# regulator.net
KiCad netlist of a schematic drawn in Altium Designer
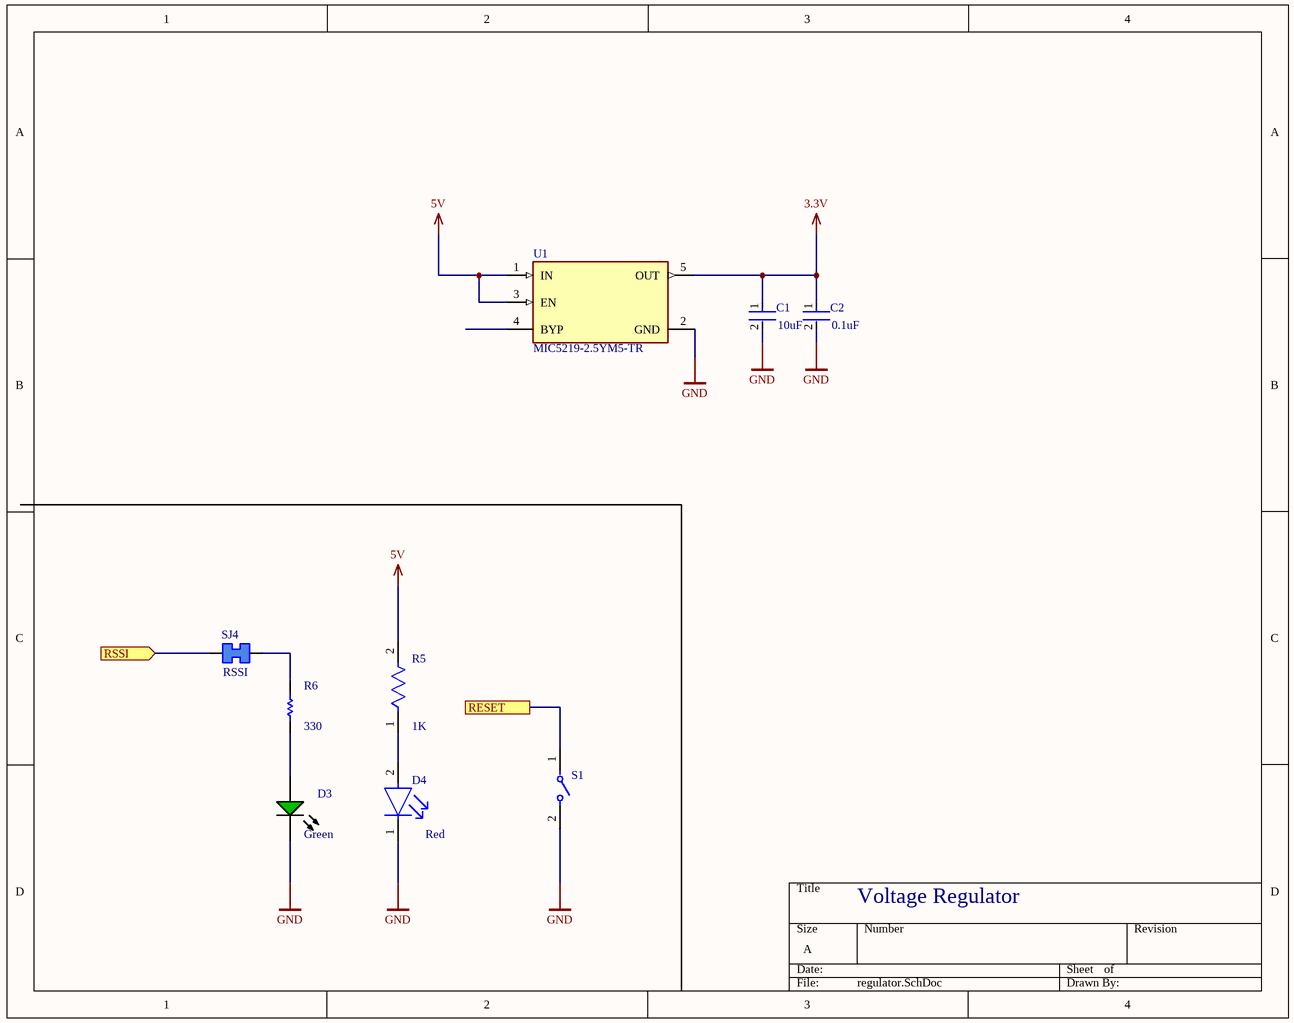
[diagram p0: regulator.SchDoc]

(export (version "E")
  (design (tool "Eeschema 10.0.6"))
  (components
    (comp (ref "C1")
      (value "10uF")
      (footprint "FP-GRM188-0_1-e0_2_0_55-IPC_A")
      (description "Chip Multilayer Ceramic Capacitors for General Purpose, 0603, 10uF, X5R, 15%, 20%, 6.3V")
      (fields (field (name "VOLTAGE") "6.3V") (field (name "TOLERANCE") "20%"))
      (libsource (lib "Altium Content Vault") (part "02cd4be3c70576c341d710602a673aa"))
    )
    (comp (ref "C2")
      (value "0.1uF")
      (footprint "FP-C0402-BB-MFG")
      (description "CAP CER 0.1UF 10V X5R 0402")
      (fields (field (name "MANUFACTURER") "Kemet") (field (name "TOLERANCE") "0.1"))
      (libsource (lib "Altium Content Vault") (part "b4654b650e69147ec39a6b967a45e02"))
    )
    (comp (ref "D3")
      (value "Green")
      (footprint "AVAG-HSMX-C170_V")
      (description "Chip LED, Green, 2.2 V, -40 to 85 degC, 2-Pin SMD, Pb-Free, Tape and Reel")
      (fields (field (name "MANUFACTURER") "Avago"))
      (libsource (lib "Altium Content Vault") (part "LED_GREEN_A1K2-2"))
    )
    (comp (ref "D4")
      (value "Red")
      (footprint "FP-HSMS-C150-MFG")
      (description "LED RED DIFFUSED CHIP SMD")
      (libsource (lib "Altium Content Vault") (part "8706943c75ba83719d021d2fdc84c58"))
    )
    (comp (ref "R5")
      (value "1K")
      (footprint "FP-ERJ1GN-IPC_C")
      (description "RES SMD 1K OHM 1% 1/20W 0201")
      (fields (field (name "TOLERANCE") "1%"))
      (libsource (lib "Altium Content Vault") (part "1029c3af85768c4190bb7ad29bc67b5"))
    )
    (comp (ref "R6")
      (value "330")
      (footprint "RESC0603X26X15ML03T05")
      (fields (field (name "PART NUMBER") "ERJ1GNF3300C") (field (name "MANUFACTURER") "Panasonic"))
      (libsource (lib "Altium Content Vault") (part "RES"))
    )
    (comp (ref "S1")
      (value "~")
      (footprint "FP-B3F-6022-MFG")
      (description "SWITCH TACTILE SPST-NO 0.05A 24V")
      (libsource (lib "Altium Content Vault") (part "bb27bde45df87f1f469753f287ef5ae"))
    )
    (comp (ref "SJ4")
      (value "RSSI")
      (footprint "Solder Jumper-Footprint-1")
      (description "2 pad Solder Jumper")
      (libsource (lib "Shuvendu Das") (part "Solder Jumper"))
    )
    (comp (ref "U1")
      (value "MIC5219-2.5YM5-TR")
      (footprint "FP-SOT23-5LD-PL-1-MFG")
      (description "MIC5219-2.5YM5-TR LDO Regulator Pos 2.5V 0.5A 5-Pin SOT-23 T/R")
      (libsource (lib "Altium Content Vault") (part "2b4562ae194ecca3f53436ab1e355a0"))
    )
  )
  (nets
    (net (code "1") (name "/RESET") (class "Default")
      (node (ref "S1") (pin "1") (pinfunction "1_1") (pintype "passive"))
    )
    (net (code "2") (name "/RSSI") (class "Default")
      (node (ref "SJ4") (pin "1") (pinfunction "1_1") (pintype "passive"))
    )
    (net (code "3") (name "3.3V") (class "Default")
      (node (ref "C1") (pin "1") (pinfunction "1_1") (pintype "passive"))
      (node (ref "C2") (pin "1") (pinfunction "1_1") (pintype "passive"))
      (node (ref "U1") (pin "5") (pinfunction "OUT_5") (pintype "output"))
    )
    (net (code "4") (name "5V") (class "Default")
      (node (ref "R5") (pin "2") (pinfunction "2_2") (pintype "passive"))
      (node (ref "U1") (pin "1") (pinfunction "IN_1") (pintype "input"))
      (node (ref "U1") (pin "3") (pinfunction "EN_3") (pintype "input"))
    )
    (net (code "5") (name "GND") (class "Default")
      (node (ref "C1") (pin "2") (pinfunction "2_2") (pintype "passive"))
      (node (ref "C2") (pin "2") (pinfunction "2_2") (pintype "passive"))
      (node (ref "D3") (pin "2") (pinfunction "K_2") (pintype "passive"))
      (node (ref "D4") (pin "1") (pinfunction "C_1") (pintype "passive"))
      (node (ref "S1") (pin "2") (pinfunction "2_2") (pintype "passive"))
      (node (ref "U1") (pin "2") (pinfunction "GND_2") (pintype "power_in"))
    )
    (net (code "6") (name "Net-(D3-A)") (class "Default")
      (node (ref "D3") (pin "1") (pinfunction "A_1") (pintype "passive"))
      (node (ref "R6") (pin "2") (pinfunction "2_2") (pintype "passive"))
    )
    (net (code "7") (name "Net-(D4-A)") (class "Default")
      (node (ref "D4") (pin "2") (pinfunction "A_2") (pintype "passive"))
      (node (ref "R5") (pin "1") (pinfunction "1_1") (pintype "passive"))
    )
    (net (code "8") (name "Net-(R6-Pad1)") (class "Default")
      (node (ref "R6") (pin "1") (pinfunction "1_1") (pintype "passive"))
      (node (ref "SJ4") (pin "2") (pinfunction "2_2") (pintype "passive"))
    )
    (net (code "9") (name "unconnected-(U1-BYP-Pad4)") (class "Default")
      (node (ref "U1") (pin "4") (pinfunction "BYP_4") (pintype "passive"))
    )
  )
)
